# Interface_USB3.net
KiCad netlist of a schematic drawn in EAGLE
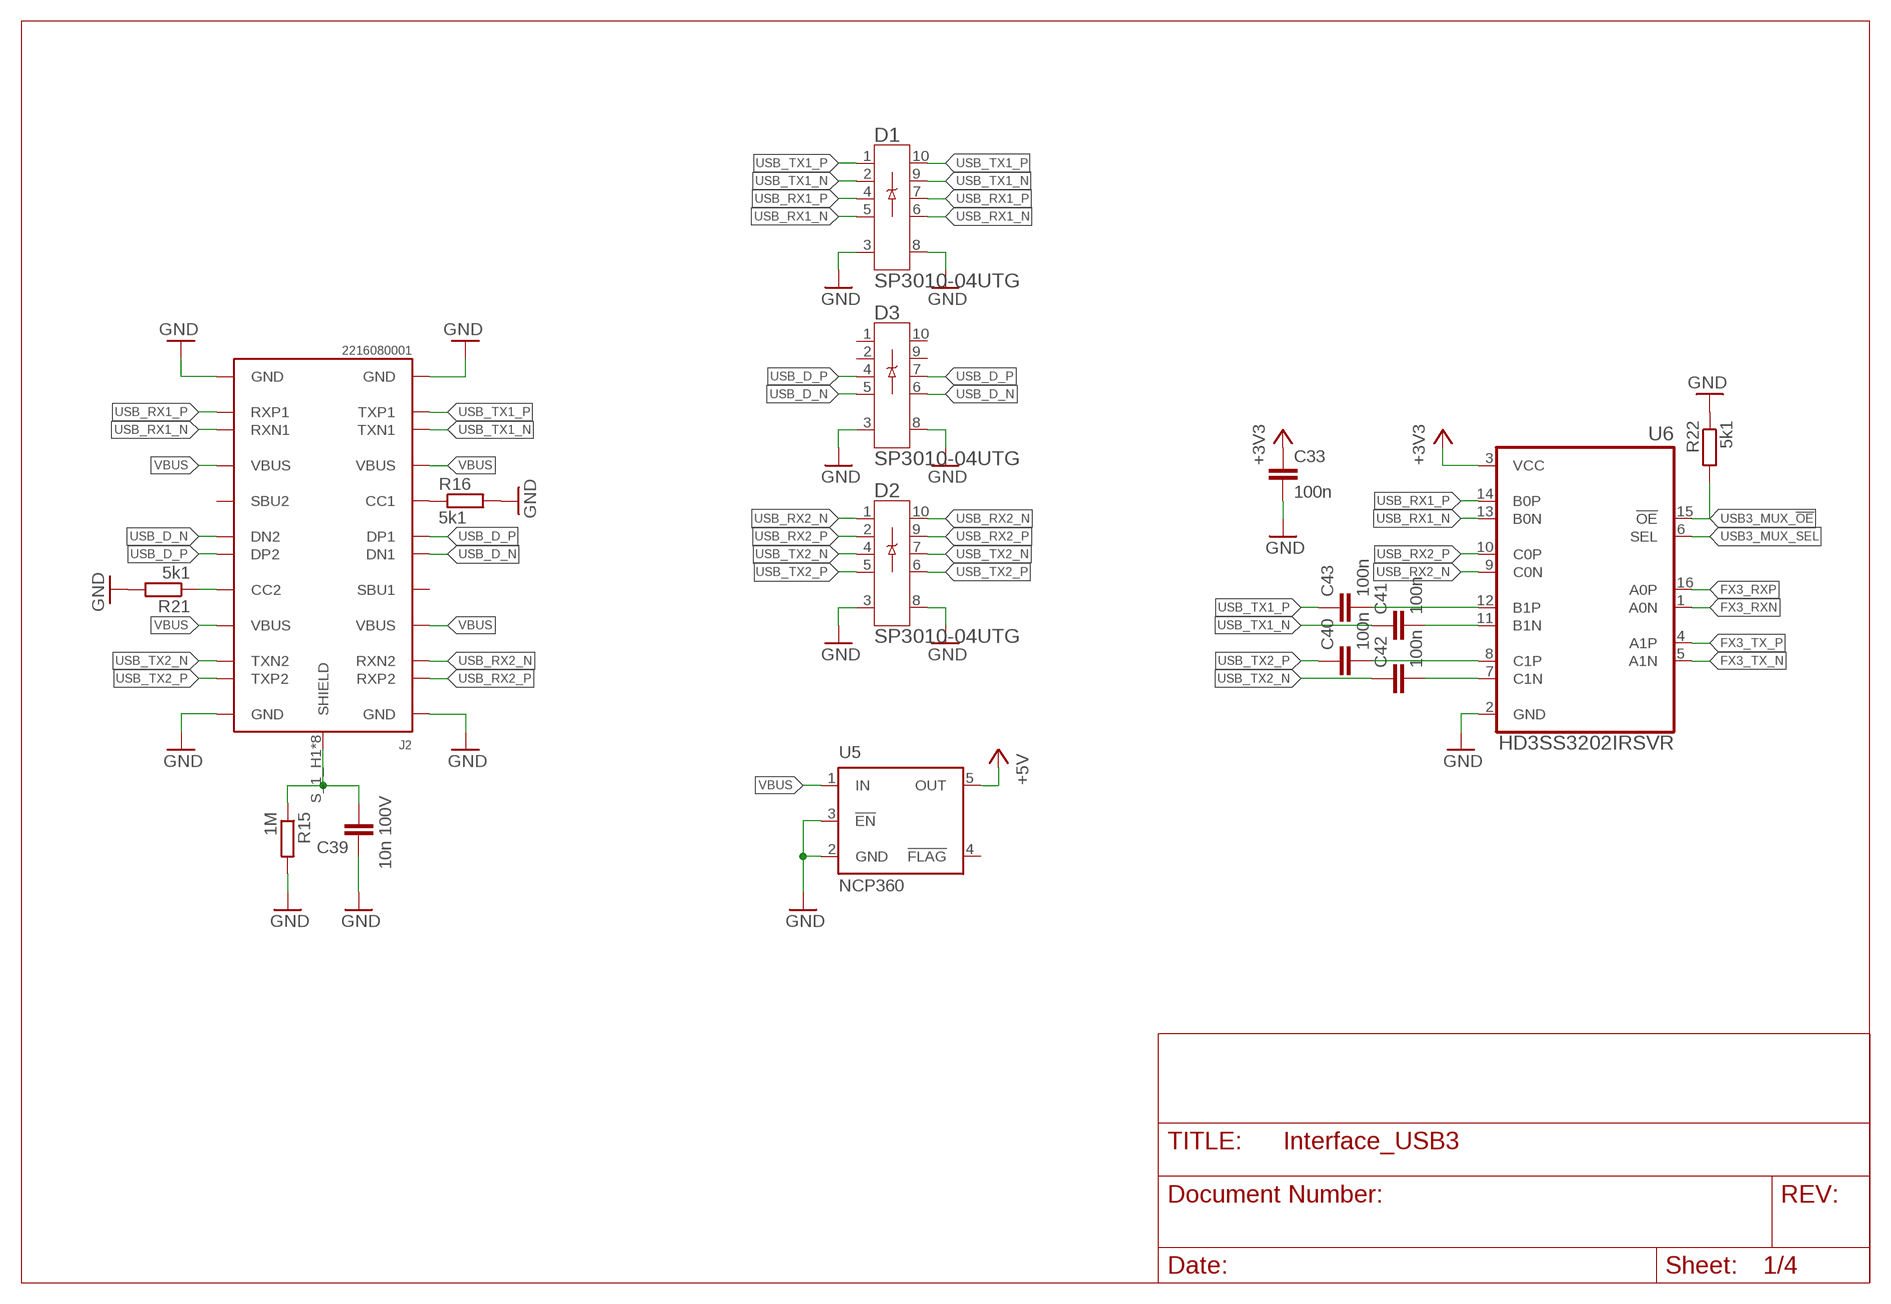
[diagram p0: schematic, sheet 1]
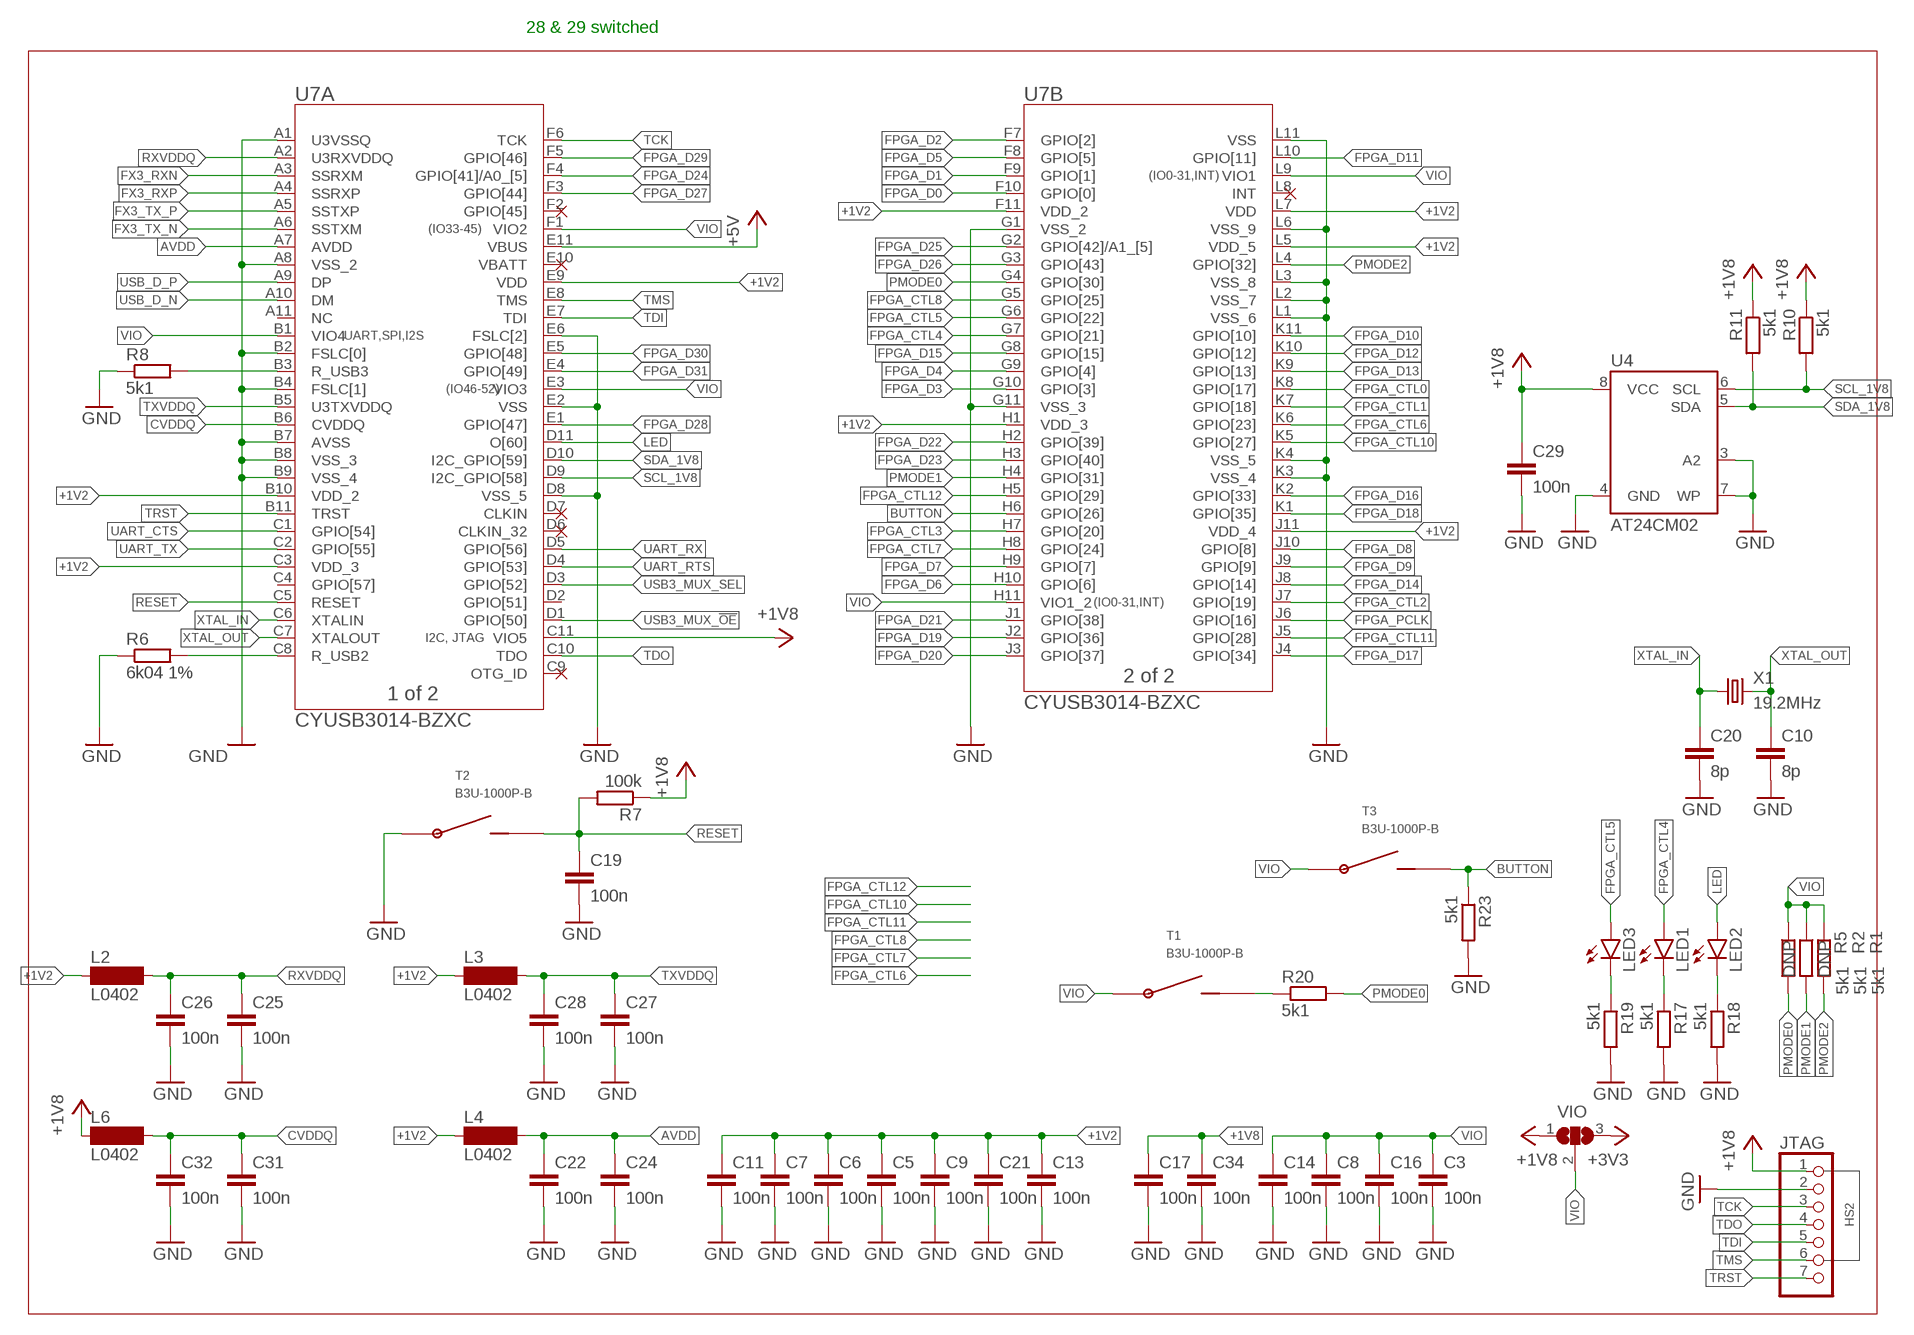
[diagram p1: schematic, sheet 2]
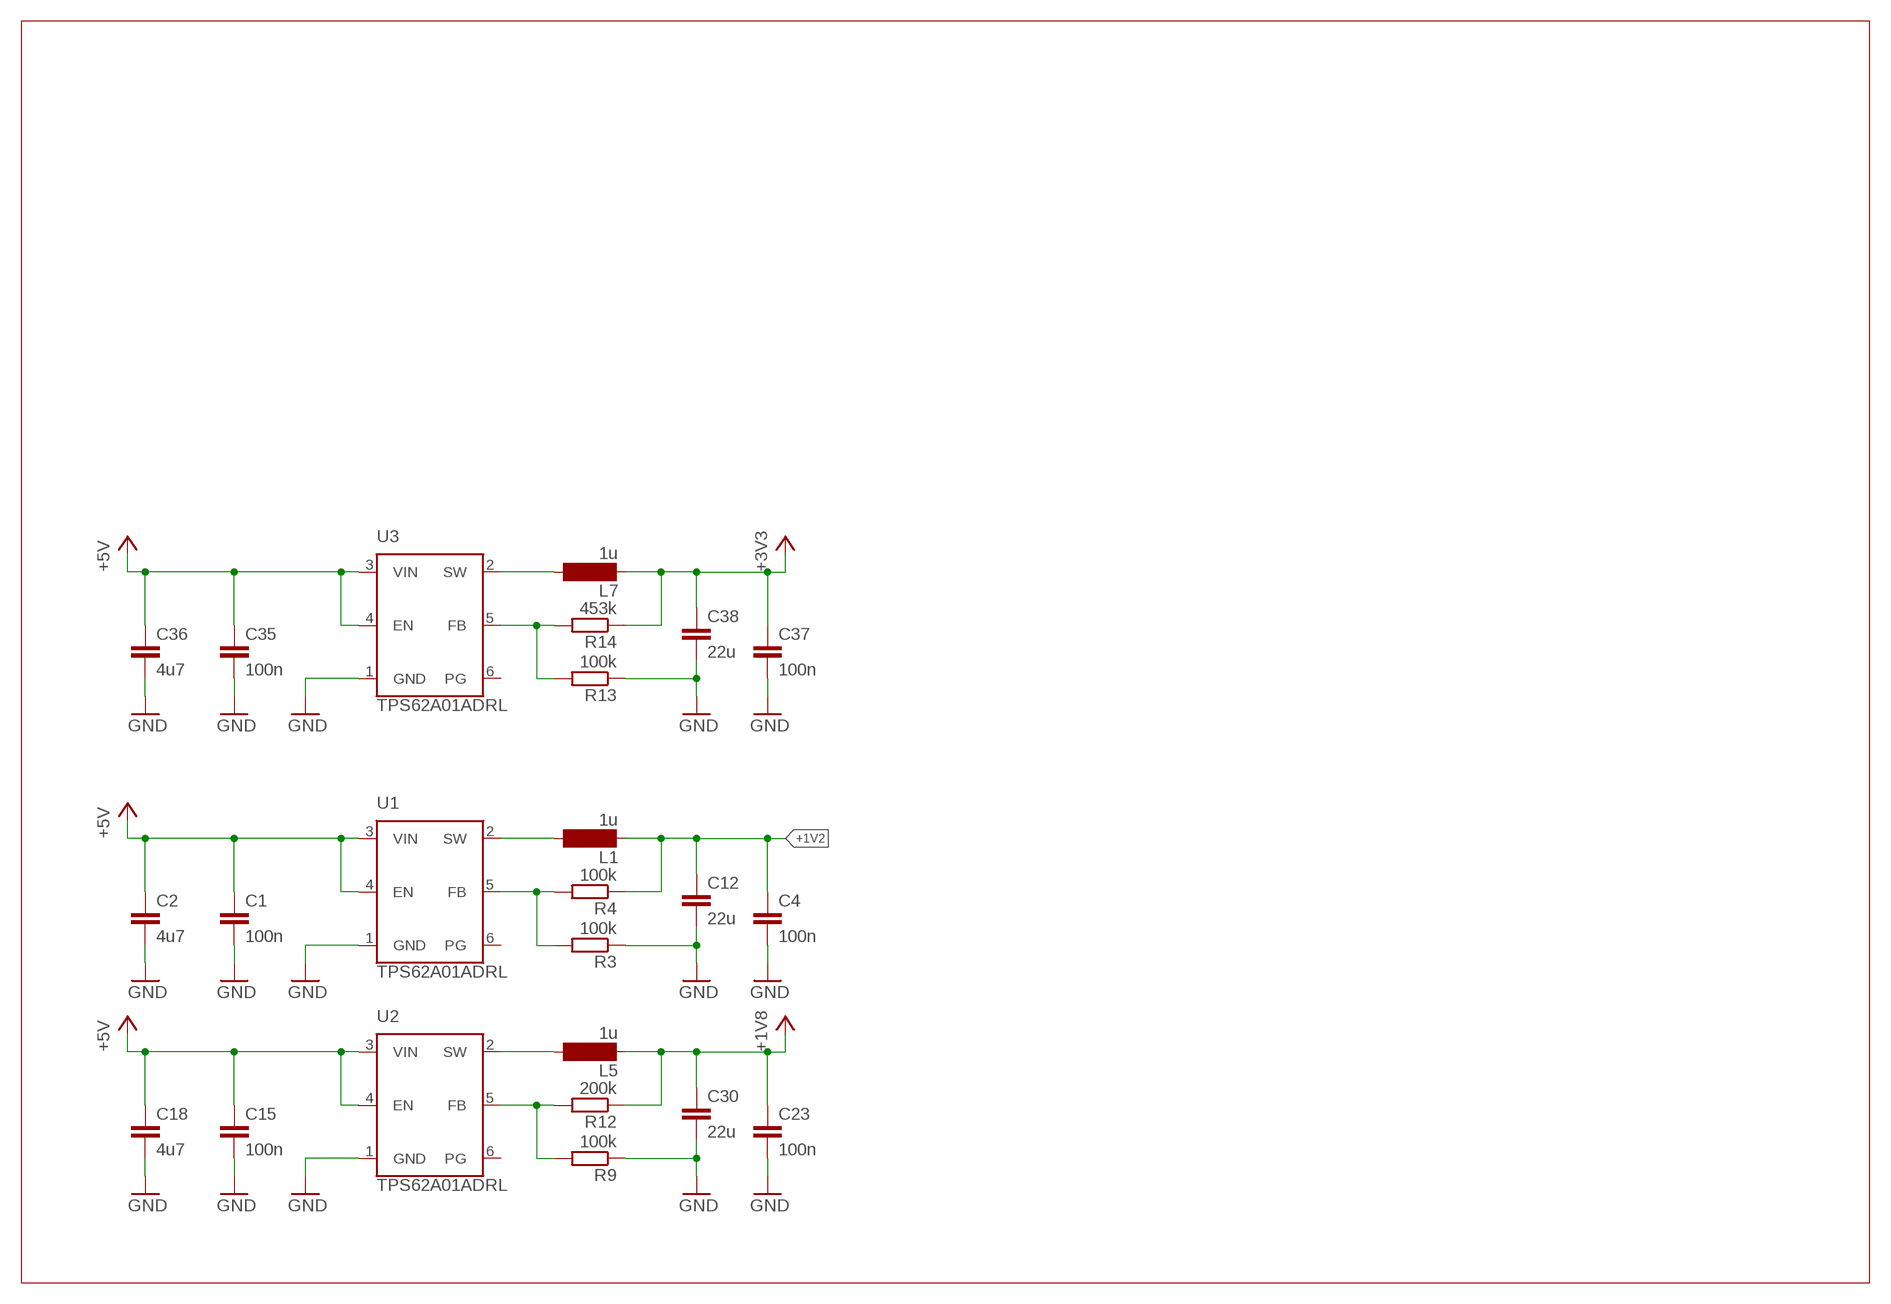
[diagram p2: schematic, sheet 3]
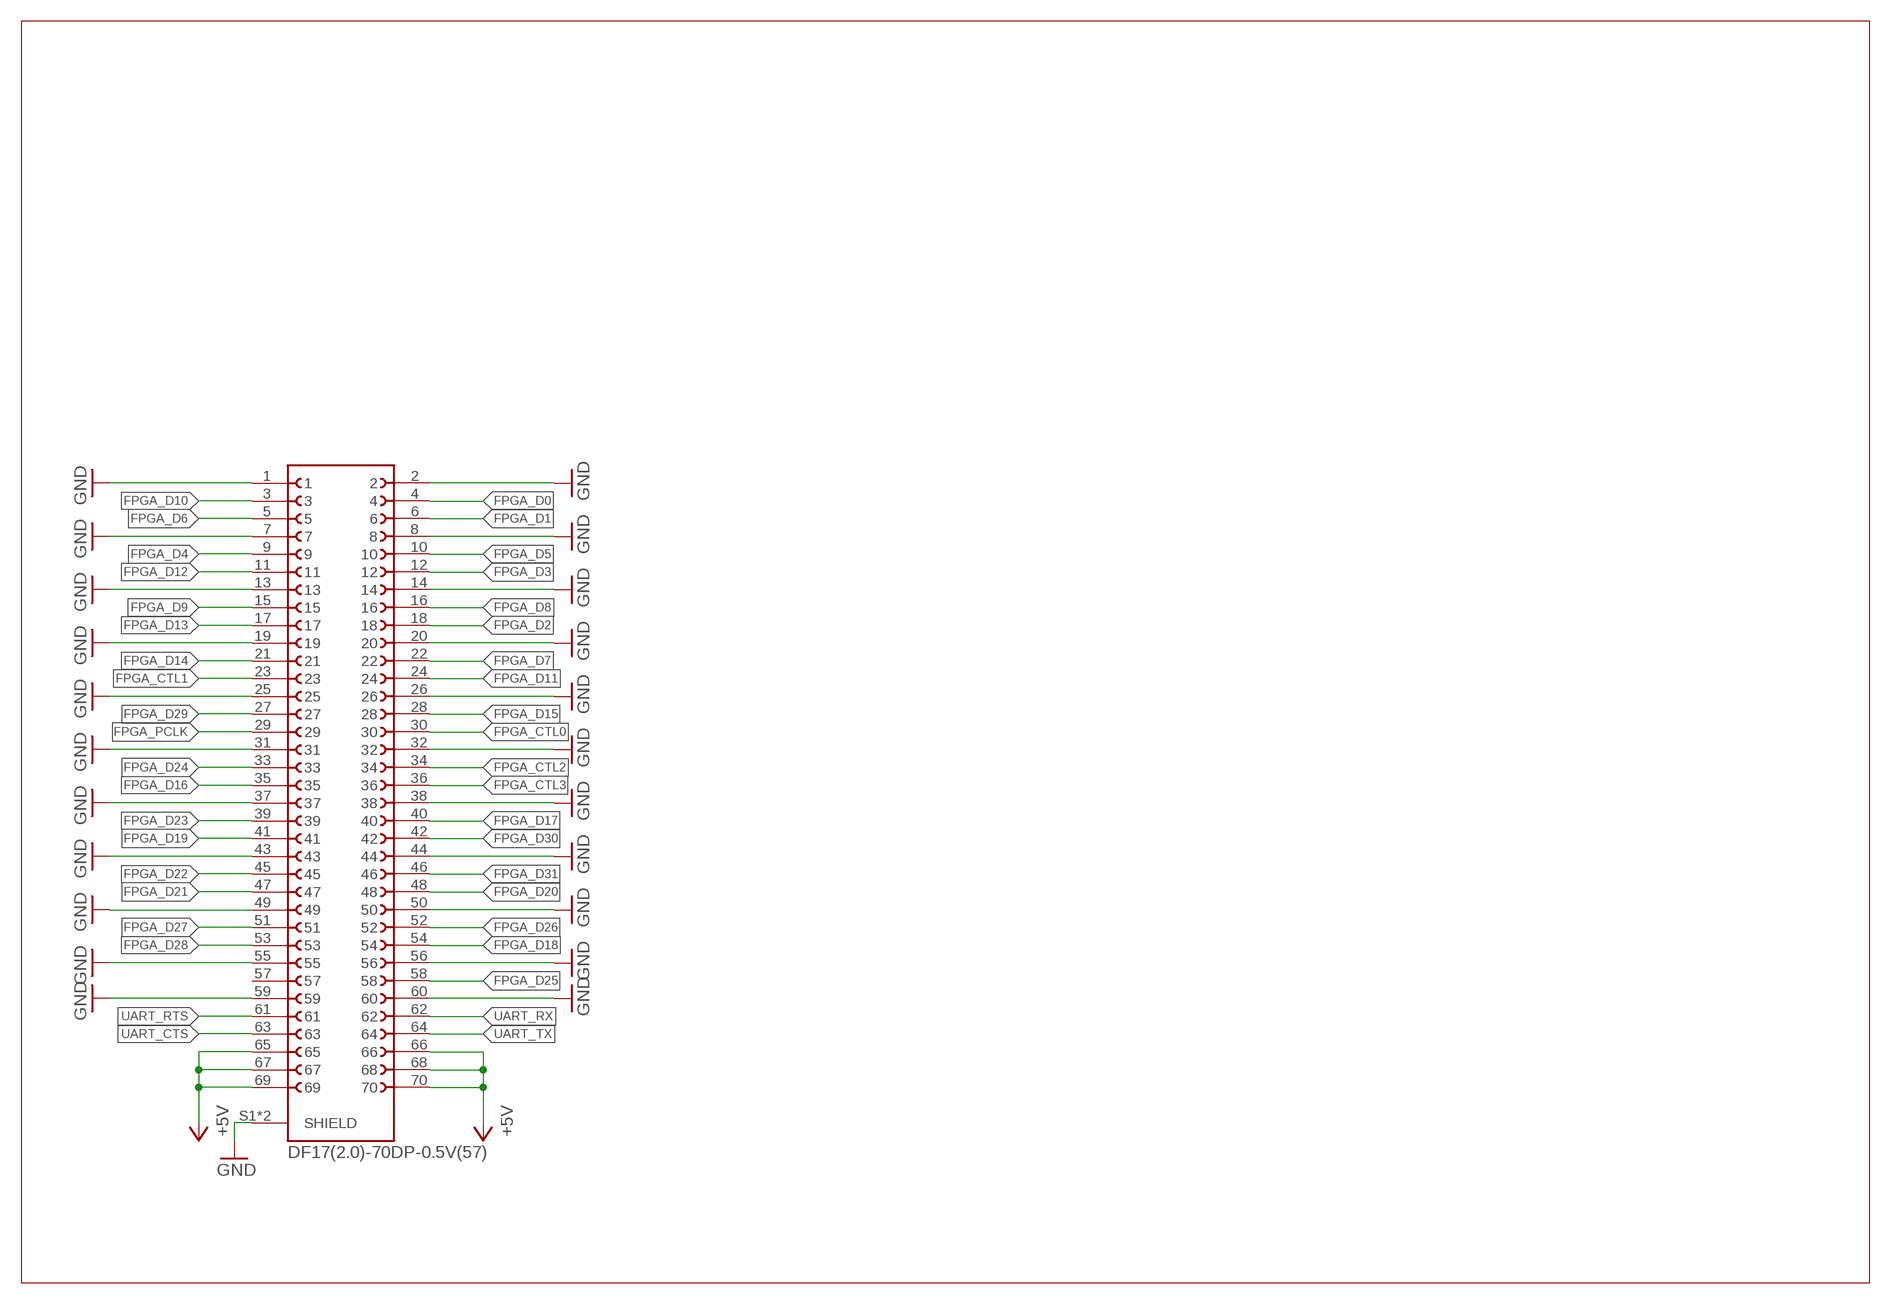
[diagram p3: schematic, sheet 4]

(export (version "E")
  (design (tool "Eeschema 10.0.6"))
  (components
    (comp (ref "C33")
      (value "100n")
      (footprint "eagle-import:C0402")
      (libsource (lib "eagle-import") (part "C0402"))
    )
    (comp (ref "C39")
      (value "10n 100V")
      (footprint "eagle-import:C0603")
      (libsource (lib "eagle-import") (part "rcl_334_C-EUC0603"))
    )
    (comp (ref "C40")
      (value "100n")
      (footprint "eagle-import:C0402")
      (libsource (lib "eagle-import") (part "C0402"))
    )
    (comp (ref "C41")
      (value "100n")
      (footprint "eagle-import:C0402")
      (libsource (lib "eagle-import") (part "C0402"))
    )
    (comp (ref "C42")
      (value "100n")
      (footprint "eagle-import:C0402")
      (libsource (lib "eagle-import") (part "C0402"))
    )
    (comp (ref "C43")
      (value "100n")
      (footprint "eagle-import:C0402")
      (libsource (lib "eagle-import") (part "C0402"))
    )
    (comp (ref "D1")
      (value "SP3010-04UTG")
      (footprint "eagle-import:UDFEN-10_MO229_LTF")
      (libsource (lib "eagle-import") (part "SP3010-04UTG"))
    )
    (comp (ref "D2")
      (value "SP3010-04UTG")
      (footprint "eagle-import:UDFEN-10_MO229_LTF")
      (libsource (lib "eagle-import") (part "SP3010-04UTG"))
    )
    (comp (ref "D3")
      (value "SP3010-04UTG")
      (footprint "eagle-import:UDFEN-10_MO229_LTF")
      (libsource (lib "eagle-import") (part "SP3010-04UTG"))
    )
    (comp (ref "J2")
      (value "2216080001")
      (footprint "eagle-import:CONN_221608-0001_MOL")
      (libsource (lib "eagle-import") (part "2216080001"))
    )
    (comp (ref "R15")
      (value "1M")
      (footprint "eagle-import:R0603")
      (libsource (lib "eagle-import") (part "R-EU_R0603"))
    )
    (comp (ref "R16")
      (value "5k1")
      (footprint "eagle-import:R0402")
      (libsource (lib "eagle-import") (part "R-EU_R0402"))
    )
    (comp (ref "R21")
      (value "5k1")
      (footprint "eagle-import:R0402")
      (libsource (lib "eagle-import") (part "R-EU_R0402"))
    )
    (comp (ref "R22")
      (value "5k1")
      (footprint "eagle-import:R0402")
      (libsource (lib "eagle-import") (part "R-EU_R0402"))
    )
    (comp (ref "U5")
      (value "NCP360")
      (footprint "eagle-import:TSOP-5")
      (libsource (lib "eagle-import") (part "NCP360"))
    )
    (comp (ref "U6")
      (value "HD3SS3202IRSVR")
      (footprint "eagle-import:QFN40P180X260X55-16N_HD3SS3202IRSVR")
      (fields (field (name "MANUFACTURER") "Texas Instruments"))
      (libsource (lib "eagle-import") (part "HD3SS3202IRSVR"))
    )
    (comp (ref "C3")
      (value "100n")
      (footprint "eagle-import:C0402")
      (libsource (lib "eagle-import") (part "C0402"))
    )
    (comp (ref "C5")
      (value "100n")
      (footprint "eagle-import:C0402")
      (libsource (lib "eagle-import") (part "C0402"))
    )
    (comp (ref "C6")
      (value "100n")
      (footprint "eagle-import:C0402")
      (libsource (lib "eagle-import") (part "C0402"))
    )
    (comp (ref "C7")
      (value "100n")
      (footprint "eagle-import:C0402")
      (libsource (lib "eagle-import") (part "C0402"))
    )
    (comp (ref "C8")
      (value "100n")
      (footprint "eagle-import:C0402")
      (libsource (lib "eagle-import") (part "C0402"))
    )
    (comp (ref "C9")
      (value "100n")
      (footprint "eagle-import:C0402")
      (libsource (lib "eagle-import") (part "C0402"))
    )
    (comp (ref "C10")
      (value "8p")
      (footprint "eagle-import:C0402")
      (libsource (lib "eagle-import") (part "C0402"))
    )
    (comp (ref "C11")
      (value "100n")
      (footprint "eagle-import:C0402")
      (libsource (lib "eagle-import") (part "C0402"))
    )
    (comp (ref "C13")
      (value "100n")
      (footprint "eagle-import:C0402")
      (libsource (lib "eagle-import") (part "C0402"))
    )
    (comp (ref "C14")
      (value "100n")
      (footprint "eagle-import:C0402")
      (libsource (lib "eagle-import") (part "C0402"))
    )
    (comp (ref "C16")
      (value "100n")
      (footprint "eagle-import:C0402")
      (libsource (lib "eagle-import") (part "C0402"))
    )
    (comp (ref "C17")
      (value "100n")
      (footprint "eagle-import:C0402")
      (libsource (lib "eagle-import") (part "C0402"))
    )
    (comp (ref "C19")
      (value "100n")
      (footprint "eagle-import:C0402")
      (libsource (lib "eagle-import") (part "C0402"))
    )
    (comp (ref "C20")
      (value "8p")
      (footprint "eagle-import:C0402")
      (libsource (lib "eagle-import") (part "C0402"))
    )
    (comp (ref "C21")
      (value "100n")
      (footprint "eagle-import:C0402")
      (libsource (lib "eagle-import") (part "C0402"))
    )
    (comp (ref "C22")
      (value "100n")
      (footprint "eagle-import:C0402")
      (libsource (lib "eagle-import") (part "C0402"))
    )
    (comp (ref "C24")
      (value "100n")
      (footprint "eagle-import:C0402")
      (libsource (lib "eagle-import") (part "C0402"))
    )
    (comp (ref "C25")
      (value "100n")
      (footprint "eagle-import:C0402")
      (libsource (lib "eagle-import") (part "C0402"))
    )
    (comp (ref "C26")
      (value "100n")
      (footprint "eagle-import:C0402")
      (libsource (lib "eagle-import") (part "C0402"))
    )
    (comp (ref "C27")
      (value "100n")
      (footprint "eagle-import:C0402")
      (libsource (lib "eagle-import") (part "C0402"))
    )
    (comp (ref "C28")
      (value "100n")
      (footprint "eagle-import:C0402")
      (libsource (lib "eagle-import") (part "C0402"))
    )
    (comp (ref "C29")
      (value "100n")
      (footprint "eagle-import:C0402")
      (libsource (lib "eagle-import") (part "C0402"))
    )
    (comp (ref "C31")
      (value "100n")
      (footprint "eagle-import:C0402")
      (libsource (lib "eagle-import") (part "C0402"))
    )
    (comp (ref "C32")
      (value "100n")
      (footprint "eagle-import:C0402")
      (libsource (lib "eagle-import") (part "C0402"))
    )
    (comp (ref "C34")
      (value "100n")
      (footprint "eagle-import:C0402")
      (libsource (lib "eagle-import") (part "C0402"))
    )
    (comp (ref "JTAG")
      (value "PINHD-1X7_2.00")
      (footprint "eagle-import:1X07M")
      (libsource (lib "eagle-import") (part "PINHD-1X7_2.00"))
    )
    (comp (ref "L2")
      (value "L0402")
      (footprint "eagle-import:C0402")
      (libsource (lib "eagle-import") (part "L0402"))
    )
    (comp (ref "L3")
      (value "L0402")
      (footprint "eagle-import:C0402")
      (libsource (lib "eagle-import") (part "L0402"))
    )
    (comp (ref "L4")
      (value "L0402")
      (footprint "eagle-import:C0402")
      (libsource (lib "eagle-import") (part "L0402"))
    )
    (comp (ref "L6")
      (value "L0402")
      (footprint "eagle-import:C0402")
      (libsource (lib "eagle-import") (part "L0402"))
    )
    (comp (ref "LED1")
      (value "LEDCHIPLED_0603")
      (footprint "eagle-import:CHIPLED_0603")
      (libsource (lib "eagle-import") (part "LEDCHIPLED_0603"))
    )
    (comp (ref "LED2")
      (value "LEDCHIPLED_0603")
      (footprint "eagle-import:CHIPLED_0603")
      (libsource (lib "eagle-import") (part "LEDCHIPLED_0603"))
    )
    (comp (ref "LED3")
      (value "LEDCHIPLED_0603")
      (footprint "eagle-import:CHIPLED_0603")
      (libsource (lib "eagle-import") (part "LEDCHIPLED_0603"))
    )
    (comp (ref "R1")
      (value "5k1")
      (footprint "eagle-import:R0402")
      (fields (field (name "DNP") "DNP"))
      (libsource (lib "eagle-import") (part "R-EU_R0402"))
    )
    (comp (ref "R2")
      (value "5k1")
      (footprint "eagle-import:R0402")
      (libsource (lib "eagle-import") (part "R-EU_R0402"))
    )
    (comp (ref "R5")
      (value "5k1")
      (footprint "eagle-import:R0402")
      (fields (field (name "DNP") "DNP"))
      (libsource (lib "eagle-import") (part "R-EU_R0402"))
    )
    (comp (ref "R6")
      (value "6k04 1%")
      (footprint "eagle-import:R0402")
      (libsource (lib "eagle-import") (part "R-EU_R0402"))
    )
    (comp (ref "R7")
      (value "100k")
      (footprint "eagle-import:R0402")
      (libsource (lib "eagle-import") (part "R-EU_R0402"))
    )
    (comp (ref "R8")
      (value "5k1")
      (footprint "eagle-import:R0402")
      (libsource (lib "eagle-import") (part "R-EU_R0402"))
    )
    (comp (ref "R10")
      (value "5k1")
      (footprint "eagle-import:R0402")
      (libsource (lib "eagle-import") (part "R-EU_R0402"))
    )
    (comp (ref "R11")
      (value "5k1")
      (footprint "eagle-import:R0402")
      (libsource (lib "eagle-import") (part "R-EU_R0402"))
    )
    (comp (ref "R17")
      (value "5k1")
      (footprint "eagle-import:R0402")
      (libsource (lib "eagle-import") (part "R-EU_R0402"))
    )
    (comp (ref "R18")
      (value "5k1")
      (footprint "eagle-import:R0402")
      (libsource (lib "eagle-import") (part "R-EU_R0402"))
    )
    (comp (ref "R19")
      (value "5k1")
      (footprint "eagle-import:R0402")
      (libsource (lib "eagle-import") (part "R-EU_R0402"))
    )
    (comp (ref "R20")
      (value "5k1")
      (footprint "eagle-import:R0402")
      (libsource (lib "eagle-import") (part "R-EU_R0402"))
    )
    (comp (ref "R23")
      (value "5k1")
      (footprint "eagle-import:R0402")
      (libsource (lib "eagle-import") (part "R-EU_R0402"))
    )
    (comp (ref "T1")
      (value "B3U-1000P-B")
      (footprint "eagle-import:B3U-1000P-B")
      (libsource (lib "eagle-import") (part "B3U-1000P-B"))
    )
    (comp (ref "T2")
      (value "B3U-1000P-B")
      (footprint "eagle-import:B3U-1000P-B")
      (libsource (lib "eagle-import") (part "B3U-1000P-B"))
    )
    (comp (ref "T3")
      (value "B3U-1000P-B")
      (footprint "eagle-import:B3U-1000P-B")
      (libsource (lib "eagle-import") (part "B3U-1000P-B"))
    )
    (comp (ref "U4")
      (value "AT24CM02")
      (footprint "eagle-import:SOIC8")
      (libsource (lib "eagle-import") (part "AT24CM02"))
    )
    (comp (ref "U7")
      (value "CYUSB3014-BZXC")
      (footprint "eagle-import:PG-TFBGA-121-800_INF")
      (fields (field (name "LCSC") "C462526"))
      (libsource (lib "eagle-import") (part "CYUSB3014-BZXC"))
    )
    (comp (ref "VIO")
      (value "SJ2W")
      (footprint "eagle-import:SJ_2")
      (libsource (lib "eagle-import") (part "SJ2W"))
    )
    (comp (ref "X1")
      (value "19.2MHz")
      (footprint "eagle-import:2520")
      (libsource (lib "eagle-import") (part "CRYSTAL-2520"))
    )
    (comp (ref "C1")
      (value "100n")
      (footprint "eagle-import:C0402")
      (libsource (lib "eagle-import") (part "C0402"))
    )
    (comp (ref "C2")
      (value "4u7")
      (footprint "eagle-import:C0603")
      (libsource (lib "eagle-import") (part "C-EUC0603"))
    )
    (comp (ref "C4")
      (value "100n")
      (footprint "eagle-import:C0402")
      (libsource (lib "eagle-import") (part "C0402"))
    )
    (comp (ref "C12")
      (value "22u")
      (footprint "eagle-import:C0603")
      (libsource (lib "eagle-import") (part "C-EUC0603"))
    )
    (comp (ref "C15")
      (value "100n")
      (footprint "eagle-import:C0402")
      (libsource (lib "eagle-import") (part "C0402"))
    )
    (comp (ref "C18")
      (value "4u7")
      (footprint "eagle-import:C0603")
      (libsource (lib "eagle-import") (part "C-EUC0603"))
    )
    (comp (ref "C23")
      (value "100n")
      (footprint "eagle-import:C0402")
      (libsource (lib "eagle-import") (part "C0402"))
    )
    (comp (ref "C30")
      (value "22u")
      (footprint "eagle-import:C0603")
      (libsource (lib "eagle-import") (part "C-EUC0603"))
    )
    (comp (ref "C35")
      (value "100n")
      (footprint "eagle-import:C0402")
      (libsource (lib "eagle-import") (part "C0402"))
    )
    (comp (ref "C36")
      (value "4u7")
      (footprint "eagle-import:C0603")
      (libsource (lib "eagle-import") (part "C-EUC0603"))
    )
    (comp (ref "C37")
      (value "100n")
      (footprint "eagle-import:C0402")
      (libsource (lib "eagle-import") (part "C0402"))
    )
    (comp (ref "C38")
      (value "22u")
      (footprint "eagle-import:C0603")
      (libsource (lib "eagle-import") (part "C-EUC0603"))
    )
    (comp (ref "L1")
      (value "1u")
      (footprint "eagle-import:L1008")
      (fields (field (name "MPN") "LQM2HPN1R0MG0L"))
      (libsource (lib "eagle-import") (part "L1008"))
    )
    (comp (ref "L5")
      (value "1u")
      (footprint "eagle-import:L1008")
      (fields (field (name "MPN") "LQM2HPN1R0MG0L"))
      (libsource (lib "eagle-import") (part "L1008"))
    )
    (comp (ref "L7")
      (value "1u")
      (footprint "eagle-import:L1008")
      (fields (field (name "MPN") "LQM2HPN1R0MG0L"))
      (libsource (lib "eagle-import") (part "L1008"))
    )
    (comp (ref "R3")
      (value "100k")
      (footprint "eagle-import:R0402")
      (libsource (lib "eagle-import") (part "R-EU_R0402"))
    )
    (comp (ref "R4")
      (value "100k")
      (footprint "eagle-import:R0402")
      (libsource (lib "eagle-import") (part "R-EU_R0402"))
    )
    (comp (ref "R9")
      (value "100k")
      (footprint "eagle-import:R0402")
      (libsource (lib "eagle-import") (part "R-EU_R0402"))
    )
    (comp (ref "R12")
      (value "200k")
      (footprint "eagle-import:R0402")
      (libsource (lib "eagle-import") (part "R-EU_R0402"))
    )
    (comp (ref "R13")
      (value "100k")
      (footprint "eagle-import:R0402")
      (libsource (lib "eagle-import") (part "R-EU_R0402"))
    )
    (comp (ref "R14")
      (value "453k")
      (footprint "eagle-import:R0402")
      (libsource (lib "eagle-import") (part "R-EU_R0402"))
    )
    (comp (ref "U1")
      (value "TPS62A01ADRL")
      (footprint "eagle-import:SOTFL50P160X60-6N")
      (fields (field (name "MANUFACTURER_PART_NUMBER") "TPS62A01ADRLR"))
      (libsource (lib "eagle-import") (part "TPS62A01ADRL"))
    )
    (comp (ref "U2")
      (value "TPS62A01ADRL")
      (footprint "eagle-import:SOTFL50P160X60-6N")
      (fields (field (name "MANUFACTURER_PART_NUMBER") "TPS62A01ADRLR"))
      (libsource (lib "eagle-import") (part "TPS62A01ADRL"))
    )
    (comp (ref "U3")
      (value "TPS62A01ADRL")
      (footprint "eagle-import:SOTFL50P160X60-6N")
      (fields (field (name "MANUFACTURER_PART_NUMBER") "TPS62A01ADRLR"))
      (libsource (lib "eagle-import") (part "TPS62A01ADRL"))
    )
    (comp (ref "J1")
      (value "DF17(2.0)-70DP-0.5V(57)")
      (footprint "eagle-import:DF17(2.0)-70DP-0.5V(57)")
      (libsource (lib "eagle-import") (part "DF17(2.0)-70DP-0.5V(57)"))
    )
  )
  (nets
    (net (code "1") (name "+1V2") (class "Default")
      (node (ref "C11") (pin "1") (pinfunction "1_1") (pintype "passive"))
      (node (ref "C12") (pin "1") (pinfunction "1_1") (pintype "passive"))
      (node (ref "C13") (pin "1") (pinfunction "1_1") (pintype "passive"))
      (node (ref "C21") (pin "1") (pinfunction "1_1") (pintype "passive"))
      (node (ref "C4") (pin "1") (pinfunction "1_1") (pintype "passive"))
      (node (ref "C5") (pin "1") (pinfunction "1_1") (pintype "passive"))
      (node (ref "C6") (pin "1") (pinfunction "1_1") (pintype "passive"))
      (node (ref "C7") (pin "1") (pinfunction "1_1") (pintype "passive"))
      (node (ref "C9") (pin "1") (pinfunction "1_1") (pintype "passive"))
      (node (ref "L1") (pin "1") (pinfunction "1_1") (pintype "passive"))
      (node (ref "L2") (pin "1") (pinfunction "1_1") (pintype "passive"))
      (node (ref "L3") (pin "1") (pinfunction "1_1") (pintype "passive"))
      (node (ref "L4") (pin "1") (pinfunction "1_1") (pintype "passive"))
      (node (ref "R4") (pin "1") (pinfunction "1_1") (pintype "passive"))
      (node (ref "U7") (pin "B10") (pinfunction "VDD_2_B10") (pintype "power_in"))
      (node (ref "U7") (pin "C3") (pinfunction "VDD_3_C3") (pintype "power_in"))
      (node (ref "U7") (pin "E9") (pinfunction "VDD_E9") (pintype "power_in"))
      (node (ref "U7") (pin "F11") (pinfunction "VDD_2_F11") (pintype "power_in"))
      (node (ref "U7") (pin "H1") (pinfunction "VDD_3_H1") (pintype "power_in"))
      (node (ref "U7") (pin "J11") (pinfunction "VDD_4_J11") (pintype "power_in"))
      (node (ref "U7") (pin "L5") (pinfunction "VDD_5_L5") (pintype "power_in"))
      (node (ref "U7") (pin "L7") (pinfunction "VDD_L7") (pintype "power_in"))
    )
    (net (code "2") (name "+1V8") (class "Default")
      (node (ref "C17") (pin "1") (pinfunction "1_1") (pintype "passive"))
      (node (ref "C23") (pin "1") (pinfunction "1_1") (pintype "passive"))
      (node (ref "C29") (pin "1") (pinfunction "1_1") (pintype "passive"))
      (node (ref "C30") (pin "1") (pinfunction "1_1") (pintype "passive"))
      (node (ref "C34") (pin "1") (pinfunction "1_1") (pintype "passive"))
      (node (ref "JTAG") (pin "1") (pinfunction "1_1") (pintype "passive"))
      (node (ref "L5") (pin "1") (pinfunction "1_1") (pintype "passive"))
      (node (ref "L6") (pin "1") (pinfunction "1_1") (pintype "passive"))
      (node (ref "R10") (pin "1") (pinfunction "1_1") (pintype "passive"))
      (node (ref "R11") (pin "1") (pinfunction "1_1") (pintype "passive"))
      (node (ref "R12") (pin "1") (pinfunction "1_1") (pintype "passive"))
      (node (ref "R7") (pin "1") (pinfunction "1_1") (pintype "passive"))
      (node (ref "U4") (pin "8") (pinfunction "VCC_8") (pintype "power_in"))
      (node (ref "U7") (pin "C11") (pinfunction "VIO5_C11") (pintype "bidirectional"))
      (node (ref "VIO") (pin "1") (pinfunction "1_1") (pintype "passive"))
    )
    (net (code "3") (name "+3V3") (class "Default")
      (node (ref "C33") (pin "1") (pinfunction "1_1") (pintype "passive"))
      (node (ref "C37") (pin "1") (pinfunction "1_1") (pintype "passive"))
      (node (ref "C38") (pin "1") (pinfunction "1_1") (pintype "passive"))
      (node (ref "L7") (pin "1") (pinfunction "1_1") (pintype "passive"))
      (node (ref "R14") (pin "1") (pinfunction "1_1") (pintype "passive"))
      (node (ref "U6") (pin "3") (pinfunction "VCC_3") (pintype "power_in"))
      (node (ref "VIO") (pin "3") (pinfunction "3_3") (pintype "passive"))
    )
    (net (code "4") (name "+5V") (class "Default")
      (node (ref "C1") (pin "1") (pinfunction "1_1") (pintype "passive"))
      (node (ref "C15") (pin "1") (pinfunction "1_1") (pintype "passive"))
      (node (ref "C18") (pin "1") (pinfunction "1_1") (pintype "passive"))
      (node (ref "C2") (pin "1") (pinfunction "1_1") (pintype "passive"))
      (node (ref "C35") (pin "1") (pinfunction "1_1") (pintype "passive"))
      (node (ref "C36") (pin "1") (pinfunction "1_1") (pintype "passive"))
      (node (ref "J1") (pin "65") (pinfunction "65_65") (pintype "passive"))
      (node (ref "J1") (pin "66") (pinfunction "66_66") (pintype "passive"))
      (node (ref "J1") (pin "67") (pinfunction "67_67") (pintype "passive"))
      (node (ref "J1") (pin "68") (pinfunction "68_68") (pintype "passive"))
      (node (ref "J1") (pin "69") (pinfunction "69_69") (pintype "passive"))
      (node (ref "J1") (pin "70") (pinfunction "70_70") (pintype "passive"))
      (node (ref "U1") (pin "3") (pinfunction "VIN_3") (pintype "bidirectional"))
      (node (ref "U1") (pin "4") (pinfunction "EN_4") (pintype "bidirectional"))
      (node (ref "U2") (pin "3") (pinfunction "VIN_3") (pintype "bidirectional"))
      (node (ref "U2") (pin "4") (pinfunction "EN_4") (pintype "bidirectional"))
      (node (ref "U3") (pin "3") (pinfunction "VIN_3") (pintype "bidirectional"))
      (node (ref "U3") (pin "4") (pinfunction "EN_4") (pintype "bidirectional"))
      (node (ref "U5") (pin "5") (pinfunction "OUT_5") (pintype "passive"))
      (node (ref "U7") (pin "E11") (pinfunction "VBUS_E11") (pintype "power_in"))
    )
    (net (code "5") (name "AVDD") (class "Default")
      (node (ref "C22") (pin "1") (pinfunction "1_1") (pintype "passive"))
      (node (ref "C24") (pin "1") (pinfunction "1_1") (pintype "passive"))
      (node (ref "L4") (pin "2") (pinfunction "2_2") (pintype "passive"))
      (node (ref "U7") (pin "A7") (pinfunction "AVDD_A7") (pintype "power_in"))
    )
    (net (code "6") (name "BUTTON") (class "Default")
      (node (ref "R23") (pin "1") (pinfunction "1_1") (pintype "passive"))
      (node (ref "T3") (pin "P$2") (pinfunction "P$2_P$2") (pintype "bidirectional"))
      (node (ref "U7") (pin "H6") (pinfunction "GPIO[26]_H6") (pintype "bidirectional"))
    )
    (net (code "7") (name "CVDDQ") (class "Default")
      (node (ref "C31") (pin "1") (pinfunction "1_1") (pintype "passive"))
      (node (ref "C32") (pin "1") (pinfunction "1_1") (pintype "passive"))
      (node (ref "L6") (pin "2") (pinfunction "2_2") (pintype "passive"))
      (node (ref "U7") (pin "B6") (pinfunction "CVDDQ_B6") (pintype "power_in"))
    )
    (net (code "8") (name "FPGA_CTL0") (class "Default")
      (node (ref "J1") (pin "30") (pinfunction "30_30") (pintype "passive"))
      (node (ref "U7") (pin "K8") (pinfunction "GPIO[17]_K8") (pintype "bidirectional"))
    )
    (net (code "9") (name "FPGA_CTL1") (class "Default")
      (node (ref "J1") (pin "23") (pinfunction "23_23") (pintype "passive"))
      (node (ref "U7") (pin "K7") (pinfunction "GPIO[18]_K7") (pintype "bidirectional"))
    )
    (net (code "10") (name "FPGA_CTL2") (class "Default")
      (node (ref "J1") (pin "34") (pinfunction "34_34") (pintype "passive"))
      (node (ref "U7") (pin "J7") (pinfunction "GPIO[19]_J7") (pintype "bidirectional"))
    )
    (net (code "11") (name "FPGA_CTL3") (class "Default")
      (node (ref "J1") (pin "36") (pinfunction "36_36") (pintype "passive"))
      (node (ref "U7") (pin "H7") (pinfunction "GPIO[20]_H7") (pintype "bidirectional"))
    )
    (net (code "12") (name "FPGA_CTL4") (class "Default")
      (node (ref "LED1") (pin "A") (pinfunction "A_A") (pintype "passive"))
      (node (ref "U7") (pin "G7") (pinfunction "GPIO[21]_G7") (pintype "bidirectional"))
    )
    (net (code "13") (name "FPGA_CTL5") (class "Default")
      (node (ref "LED3") (pin "A") (pinfunction "A_A") (pintype "passive"))
      (node (ref "U7") (pin "G6") (pinfunction "GPIO[22]_G6") (pintype "bidirectional"))
    )
    (net (code "14") (name "FPGA_CTL6") (class "Default")
      (node (ref "U7") (pin "K6") (pinfunction "GPIO[23]_K6") (pintype "bidirectional"))
    )
    (net (code "15") (name "FPGA_CTL7") (class "Default")
      (node (ref "U7") (pin "H8") (pinfunction "GPIO[24]_H8") (pintype "bidirectional"))
    )
    (net (code "16") (name "FPGA_CTL8") (class "Default")
      (node (ref "U7") (pin "G5") (pinfunction "GPIO[25]_G5") (pintype "bidirectional"))
    )
    (net (code "17") (name "FPGA_CTL10") (class "Default")
      (node (ref "U7") (pin "K5") (pinfunction "GPIO[27]_K5") (pintype "bidirectional"))
    )
    (net (code "18") (name "FPGA_CTL11") (class "Default")
      (node (ref "U7") (pin "J5") (pinfunction "GPIO[28]_J5") (pintype "bidirectional"))
    )
    (net (code "19") (name "FPGA_CTL12") (class "Default")
      (node (ref "U7") (pin "H5") (pinfunction "GPIO[29]_H5") (pintype "bidirectional"))
    )
    (net (code "20") (name "FPGA_D0") (class "Default")
      (node (ref "J1") (pin "4") (pinfunction "4_4") (pintype "passive"))
      (node (ref "U7") (pin "F10") (pinfunction "GPIO[0]_F10") (pintype "bidirectional"))
    )
    (net (code "21") (name "FPGA_D1") (class "Default")
      (node (ref "J1") (pin "6") (pinfunction "6_6") (pintype "passive"))
      (node (ref "U7") (pin "F9") (pinfunction "GPIO[1]_F9") (pintype "bidirectional"))
    )
    (net (code "22") (name "FPGA_D2") (class "Default")
      (node (ref "J1") (pin "18") (pinfunction "18_18") (pintype "passive"))
      (node (ref "U7") (pin "F7") (pinfunction "GPIO[2]_F7") (pintype "bidirectional"))
    )
    (net (code "23") (name "FPGA_D3") (class "Default")
      (node (ref "J1") (pin "12") (pinfunction "12_12") (pintype "passive"))
      (node (ref "U7") (pin "G10") (pinfunction "GPIO[3]_G10") (pintype "bidirectional"))
    )
    (net (code "24") (name "FPGA_D4") (class "Default")
      (node (ref "J1") (pin "9") (pinfunction "9_9") (pintype "passive"))
      (node (ref "U7") (pin "G9") (pinfunction "GPIO[4]_G9") (pintype "bidirectional"))
    )
    (net (code "25") (name "FPGA_D5") (class "Default")
      (node (ref "J1") (pin "10") (pinfunction "10_10") (pintype "passive"))
      (node (ref "U7") (pin "F8") (pinfunction "GPIO[5]_F8") (pintype "bidirectional"))
    )
    (net (code "26") (name "FPGA_D6") (class "Default")
      (node (ref "J1") (pin "5") (pinfunction "5_5") (pintype "passive"))
      (node (ref "U7") (pin "H10") (pinfunction "GPIO[6]_H10") (pintype "bidirectional"))
    )
    (net (code "27") (name "FPGA_D7") (class "Default")
      (node (ref "J1") (pin "22") (pinfunction "22_22") (pintype "passive"))
      (node (ref "U7") (pin "H9") (pinfunction "GPIO[7]_H9") (pintype "bidirectional"))
    )
    (net (code "28") (name "FPGA_D8") (class "Default")
      (node (ref "J1") (pin "16") (pinfunction "16_16") (pintype "passive"))
      (node (ref "U7") (pin "J10") (pinfunction "GPIO[8]_J10") (pintype "bidirectional"))
    )
    (net (code "29") (name "FPGA_D9") (class "Default")
      (node (ref "J1") (pin "15") (pinfunction "15_15") (pintype "passive"))
      (node (ref "U7") (pin "J9") (pinfunction "GPIO[9]_J9") (pintype "bidirectional"))
    )
    (net (code "30") (name "FPGA_D10") (class "Default")
      (node (ref "J1") (pin "3") (pinfunction "3_3") (pintype "passive"))
      (node (ref "U7") (pin "K11") (pinfunction "GPIO[10]_K11") (pintype "bidirectional"))
    )
    (net (code "31") (name "FPGA_D11") (class "Default")
      (node (ref "J1") (pin "24") (pinfunction "24_24") (pintype "passive"))
      (node (ref "U7") (pin "L10") (pinfunction "GPIO[11]_L10") (pintype "bidirectional"))
    )
    (net (code "32") (name "FPGA_D12") (class "Default")
      (node (ref "J1") (pin "11") (pinfunction "11_11") (pintype "passive"))
      (node (ref "U7") (pin "K10") (pinfunction "GPIO[12]_K10") (pintype "bidirectional"))
    )
    (net (code "33") (name "FPGA_D13") (class "Default")
      (node (ref "J1") (pin "17") (pinfunction "17_17") (pintype "passive"))
      (node (ref "U7") (pin "K9") (pinfunction "GPIO[13]_K9") (pintype "bidirectional"))
    )
    (net (code "34") (name "FPGA_D14") (class "Default")
      (node (ref "J1") (pin "21") (pinfunction "21_21") (pintype "passive"))
      (node (ref "U7") (pin "J8") (pinfunction "GPIO[14]_J8") (pintype "bidirectional"))
    )
    (net (code "35") (name "FPGA_D15") (class "Default")
      (node (ref "J1") (pin "28") (pinfunction "28_28") (pintype "passive"))
      (node (ref "U7") (pin "G8") (pinfunction "GPIO[15]_G8") (pintype "bidirectional"))
    )
    (net (code "36") (name "FPGA_D16") (class "Default")
      (node (ref "J1") (pin "35") (pinfunction "35_35") (pintype "passive"))
      (node (ref "U7") (pin "K2") (pinfunction "GPIO[33]_K2") (pintype "bidirectional"))
    )
    (net (code "37") (name "FPGA_D17") (class "Default")
      (node (ref "J1") (pin "40") (pinfunction "40_40") (pintype "passive"))
      (node (ref "U7") (pin "J4") (pinfunction "GPIO[34]_J4") (pintype "bidirectional"))
    )
    (net (code "38") (name "FPGA_D18") (class "Default")
      (node (ref "J1") (pin "54") (pinfunction "54_54") (pintype "passive"))
      (node (ref "U7") (pin "K1") (pinfunction "GPIO[35]_K1") (pintype "bidirectional"))
    )
    (net (code "39") (name "FPGA_D19") (class "Default")
      (node (ref "J1") (pin "41") (pinfunction "41_41") (pintype "passive"))
      (node (ref "U7") (pin "J2") (pinfunction "GPIO[36]_J2") (pintype "bidirectional"))
    )
    (net (code "40") (name "FPGA_D20") (class "Default")
      (node (ref "J1") (pin "48") (pinfunction "48_48") (pintype "passive"))
      (node (ref "U7") (pin "J3") (pinfunction "GPIO[37]_J3") (pintype "bidirectional"))
    )
    (net (code "41") (name "FPGA_D21") (class "Default")
      (node (ref "J1") (pin "47") (pinfunction "47_47") (pintype "passive"))
      (node (ref "U7") (pin "J1") (pinfunction "GPIO[38]_J1") (pintype "bidirectional"))
    )
    (net (code "42") (name "FPGA_D22") (class "Default")
      (node (ref "J1") (pin "45") (pinfunction "45_45") (pintype "passive"))
      (node (ref "U7") (pin "H2") (pinfunction "GPIO[39]_H2") (pintype "bidirectional"))
    )
    (net (code "43") (name "FPGA_D23") (class "Default")
      (node (ref "J1") (pin "39") (pinfunction "39_39") (pintype "passive"))
      (node (ref "U7") (pin "H3") (pinfunction "GPIO[40]_H3") (pintype "bidirectional"))
    )
    (net (code "44") (name "FPGA_D24") (class "Default")
      (node (ref "J1") (pin "33") (pinfunction "33_33") (pintype "passive"))
      (node (ref "U7") (pin "F4") (pinfunction "GPIO[41]/A0_[5]_F4") (pintype "bidirectional"))
    )
    (net (code "45") (name "FPGA_D25") (class "Default")
      (node (ref "J1") (pin "58") (pinfunction "58_58") (pintype "passive"))
      (node (ref "U7") (pin "G2") (pinfunction "GPIO[42]/A1_[5]_G2") (pintype "bidirectional"))
    )
    (net (code "46") (name "FPGA_D26") (class "Default")
      (node (ref "J1") (pin "52") (pinfunction "52_52") (pintype "passive"))
      (node (ref "U7") (pin "G3") (pinfunction "GPIO[43]_G3") (pintype "bidirectional"))
    )
    (net (code "47") (name "FPGA_D27") (class "Default")
      (node (ref "J1") (pin "51") (pinfunction "51_51") (pintype "passive"))
      (node (ref "U7") (pin "F3") (pinfunction "GPIO[44]_F3") (pintype "bidirectional"))
    )
    (net (code "48") (name "FPGA_D28") (class "Default")
      (node (ref "J1") (pin "53") (pinfunction "53_53") (pintype "passive"))
      (node (ref "U7") (pin "E1") (pinfunction "GPIO[47]_E1") (pintype "bidirectional"))
    )
    (net (code "49") (name "FPGA_D29") (class "Default")
      (node (ref "J1") (pin "27") (pinfunction "27_27") (pintype "passive"))
      (node (ref "U7") (pin "F5") (pinfunction "GPIO[46]_F5") (pintype "bidirectional"))
    )
    (net (code "50") (name "FPGA_D30") (class "Default")
      (node (ref "J1") (pin "42") (pinfunction "42_42") (pintype "passive"))
      (node (ref "U7") (pin "E5") (pinfunction "GPIO[48]_E5") (pintype "bidirectional"))
    )
    (net (code "51") (name "FPGA_D31") (class "Default")
      (node (ref "J1") (pin "46") (pinfunction "46_46") (pintype "passive"))
      (node (ref "U7") (pin "E4") (pinfunction "GPIO[49]_E4") (pintype "bidirectional"))
    )
    (net (code "52") (name "FPGA_PCLK") (class "Default")
      (node (ref "J1") (pin "29") (pinfunction "29_29") (pintype "passive"))
      (node (ref "U7") (pin "J6") (pinfunction "GPIO[16]_J6") (pintype "bidirectional"))
    )
    (net (code "53") (name "FX3_RXN") (class "Default")
      (node (ref "U6") (pin "1") (pinfunction "A0N_1") (pintype "bidirectional"))
      (node (ref "U7") (pin "A3") (pinfunction "SSRXM_A3") (pintype "input"))
    )
    (net (code "54") (name "FX3_RXP") (class "Default")
      (node (ref "U6") (pin "16") (pinfunction "A0P_16") (pintype "bidirectional"))
      (node (ref "U7") (pin "A4") (pinfunction "SSRXP_A4") (pintype "input"))
    )
    (net (code "55") (name "FX3_TX_N") (class "Default")
      (node (ref "U6") (pin "5") (pinfunction "A1N_5") (pintype "bidirectional"))
      (node (ref "U7") (pin "A6") (pinfunction "SSTXM_A6") (pintype "output"))
    )
    (net (code "56") (name "FX3_TX_P") (class "Default")
      (node (ref "U6") (pin "4") (pinfunction "A1P_4") (pintype "bidirectional"))
      (node (ref "U7") (pin "A5") (pinfunction "SSTXP_A5") (pintype "output"))
    )
    (net (code "57") (name "GND") (class "Default")
      (node (ref "C1") (pin "2") (pinfunction "2_2") (pintype "passive"))
      (node (ref "C10") (pin "2") (pinfunction "2_2") (pintype "passive"))
      (node (ref "C11") (pin "2") (pinfunction "2_2") (pintype "passive"))
      (node (ref "C12") (pin "2") (pinfunction "2_2") (pintype "passive"))
      (node (ref "C13") (pin "2") (pinfunction "2_2") (pintype "passive"))
      (node (ref "C14") (pin "2") (pinfunction "2_2") (pintype "passive"))
      (node (ref "C15") (pin "2") (pinfunction "2_2") (pintype "passive"))
      (node (ref "C16") (pin "2") (pinfunction "2_2") (pintype "passive"))
      (node (ref "C17") (pin "2") (pinfunction "2_2") (pintype "passive"))
      (node (ref "C18") (pin "2") (pinfunction "2_2") (pintype "passive"))
      (node (ref "C19") (pin "2") (pinfunction "2_2") (pintype "passive"))
      (node (ref "C2") (pin "2") (pinfunction "2_2") (pintype "passive"))
      (node (ref "C20") (pin "2") (pinfunction "2_2") (pintype "passive"))
      (node (ref "C21") (pin "2") (pinfunction "2_2") (pintype "passive"))
      (node (ref "C22") (pin "2") (pinfunction "2_2") (pintype "passive"))
      (node (ref "C23") (pin "2") (pinfunction "2_2") (pintype "passive"))
      (node (ref "C24") (pin "2") (pinfunction "2_2") (pintype "passive"))
      (node (ref "C25") (pin "2") (pinfunction "2_2") (pintype "passive"))
      (node (ref "C26") (pin "2") (pinfunction "2_2") (pintype "passive"))
      (node (ref "C27") (pin "2") (pinfunction "2_2") (pintype "passive"))
      (node (ref "C28") (pin "2") (pinfunction "2_2") (pintype "passive"))
      (node (ref "C29") (pin "2") (pinfunction "2_2") (pintype "passive"))
      (node (ref "C3") (pin "2") (pinfunction "2_2") (pintype "passive"))
      (node (ref "C30") (pin "2") (pinfunction "2_2") (pintype "passive"))
      (node (ref "C31") (pin "2") (pinfunction "2_2") (pintype "passive"))
      (node (ref "C32") (pin "2") (pinfunction "2_2") (pintype "passive"))
      (node (ref "C33") (pin "2") (pinfunction "2_2") (pintype "passive"))
      (node (ref "C34") (pin "2") (pinfunction "2_2") (pintype "passive"))
      (node (ref "C35") (pin "2") (pinfunction "2_2") (pintype "passive"))
      (node (ref "C36") (pin "2") (pinfunction "2_2") (pintype "passive"))
      (node (ref "C37") (pin "2") (pinfunction "2_2") (pintype "passive"))
      (node (ref "C38") (pin "2") (pinfunction "2_2") (pintype "passive"))
      (node (ref "C39") (pin "1") (pinfunction "1_1") (pintype "passive"))
      (node (ref "C4") (pin "2") (pinfunction "2_2") (pintype "passive"))
      (node (ref "C5") (pin "2") (pinfunction "2_2") (pintype "passive"))
      (node (ref "C6") (pin "2") (pinfunction "2_2") (pintype "passive"))
      (node (ref "C7") (pin "2") (pinfunction "2_2") (pintype "passive"))
      (node (ref "C8") (pin "2") (pinfunction "2_2") (pintype "passive"))
      (node (ref "C9") (pin "2") (pinfunction "2_2") (pintype "passive"))
      (node (ref "D1") (pin "3") (pinfunction "3_3") (pintype "passive"))
      (node (ref "D1") (pin "8") (pinfunction "8_8") (pintype "passive"))
      (node (ref "D2") (pin "3") (pinfunction "3_3") (pintype "passive"))
      (node (ref "D2") (pin "8") (pinfunction "8_8") (pintype "passive"))
      (node (ref "D3") (pin "3") (pinfunction "3_3") (pintype "passive"))
      (node (ref "D3") (pin "8") (pinfunction "8_8") (pintype "passive"))
      (node (ref "J1") (pin "1") (pinfunction "1_1") (pintype "passive"))
      (node (ref "J1") (pin "13") (pinfunction "13_13") (pintype "passive"))
      (node (ref "J1") (pin "14") (pinfunction "14_14") (pintype "passive"))
      (node (ref "J1") (pin "19") (pinfunction "19_19") (pintype "passive"))
      (node (ref "J1") (pin "2") (pinfunction "2_2") (pintype "passive"))
      (node (ref "J1") (pin "20") (pinfunction "20_20") (pintype "passive"))
      (node (ref "J1") (pin "25") (pinfunction "25_25") (pintype "passive"))
      (node (ref "J1") (pin "26") (pinfunction "26_26") (pintype "passive"))
      (node (ref "J1") (pin "31") (pinfunction "31_31") (pintype "passive"))
      (node (ref "J1") (pin "32") (pinfunction "32_32") (pintype "passive"))
      (node (ref "J1") (pin "37") (pinfunction "37_37") (pintype "passive"))
      (node (ref "J1") (pin "38") (pinfunction "38_38") (pintype "passive"))
      (node (ref "J1") (pin "43") (pinfunction "43_43") (pintype "passive"))
      (node (ref "J1") (pin "44") (pinfunction "44_44") (pintype "passive"))
      (node (ref "J1") (pin "49") (pinfunction "49_49") (pintype "passive"))
      (node (ref "J1") (pin "50") (pinfunction "50_50") (pintype "passive"))
      (node (ref "J1") (pin "55") (pinfunction "55_55") (pintype "passive"))
      (node (ref "J1") (pin "56") (pinfunction "56_56") (pintype "passive"))
      (node (ref "J1") (pin "59") (pinfunction "59_59") (pintype "passive"))
      (node (ref "J1") (pin "60") (pinfunction "60_60") (pintype "passive"))
      (node (ref "J1") (pin "7") (pinfunction "7_7") (pintype "passive"))
      (node (ref "J1") (pin "8") (pinfunction "8_8") (pintype "passive"))
      (node (ref "J1") (pin "S1") (pinfunction "SHIELD_S1") (pintype "passive"))
      (node (ref "J1") (pin "S2") (pinfunction "SHIELD_S2") (pintype "passive"))
      (node (ref "J2") (pin "A1") (pinfunction "GND_A1") (pintype "power_in"))
      (node (ref "J2") (pin "A12") (pinfunction "GND_A12") (pintype "power_in"))
      (node (ref "J2") (pin "B1") (pinfunction "GND_B1") (pintype "power_in"))
      (node (ref "J2") (pin "B12") (pinfunction "GND_B12") (pintype "power_in"))
      (node (ref "JTAG") (pin "2") (pinfunction "2_2") (pintype "passive"))
      (node (ref "R13") (pin "1") (pinfunction "1_1") (pintype "passive"))
      (node (ref "R15") (pin "2") (pinfunction "2_2") (pintype "passive"))
      (node (ref "R16") (pin "2") (pinfunction "2_2") (pintype "passive"))
      (node (ref "R17") (pin "2") (pinfunction "2_2") (pintype "passive"))
      (node (ref "R18") (pin "2") (pinfunction "2_2") (pintype "passive"))
      (node (ref "R19") (pin "2") (pinfunction "2_2") (pintype "passive"))
      (node (ref "R21") (pin "2") (pinfunction "2_2") (pintype "passive"))
      (node (ref "R22") (pin "1") (pinfunction "1_1") (pintype "passive"))
      (node (ref "R23") (pin "2") (pinfunction "2_2") (pintype "passive"))
      (node (ref "R3") (pin "1") (pinfunction "1_1") (pintype "passive"))
      (node (ref "R6") (pin "1") (pinfunction "1_1") (pintype "passive"))
      (node (ref "R8") (pin "1") (pinfunction "1_1") (pintype "passive"))
      (node (ref "R9") (pin "1") (pinfunction "1_1") (pintype "passive"))
      (node (ref "T2") (pin "P$1") (pinfunction "P$1_P$1") (pintype "bidirectional"))
      (node (ref "U1") (pin "1") (pinfunction "GND_1") (pintype "bidirectional"))
      (node (ref "U2") (pin "1") (pinfunction "GND_1") (pintype "bidirectional"))
      (node (ref "U3") (pin "1") (pinfunction "GND_1") (pintype "bidirectional"))
      (node (ref "U4") (pin "3") (pinfunction "A2_3") (pintype "input"))
      (node (ref "U4") (pin "4") (pinfunction "GND_4") (pintype "power_in"))
      (node (ref "U4") (pin "7") (pinfunction "WP_7") (pintype "input"))
      (node (ref "U5") (pin "2") (pinfunction "GND_2") (pintype "power_in"))
      (node (ref "U5") (pin "3") (pinfunction "~{EN}_3") (pintype "input"))
      (node (ref "U6") (pin "2") (pinfunction "GND_2") (pintype "power_in"))
      (node (ref "U7") (pin "A1") (pinfunction "U3VSSQ_A1") (pintype "passive"))
      (node (ref "U7") (pin "A8") (pinfunction "VSS_2_A8") (pintype "passive"))
      (node (ref "U7") (pin "B2") (pinfunction "FSLC[0]_B2") (pintype "bidirectional"))
      (node (ref "U7") (pin "B4") (pinfunction "FSLC[1]_B4") (pintype "bidirectional"))
      (node (ref "U7") (pin "B7") (pinfunction "AVSS_B7") (pintype "passive"))
      (node (ref "U7") (pin "B8") (pinfunction "VSS_3_B8") (pintype "passive"))
      (node (ref "U7") (pin "B9") (pinfunction "VSS_4_B9") (pintype "passive"))
      (node (ref "U7") (pin "D8") (pinfunction "VSS_5_D8") (pintype "passive"))
      (node (ref "U7") (pin "E2") (pinfunction "VSS_E2") (pintype "passive"))
      (node (ref "U7") (pin "E6") (pinfunction "FSLC[2]_E6") (pintype "input"))
      (node (ref "U7") (pin "G1") (pinfunction "VSS_2_G1") (pintype "passive"))
      (node (ref "U7") (pin "G11") (pinfunction "VSS_3_G11") (pintype "passive"))
      (node (ref "U7") (pin "K3") (pinfunction "VSS_4_K3") (pintype "passive"))
      (node (ref "U7") (pin "K4") (pinfunction "VSS_5_K4") (pintype "passive"))
      (node (ref "U7") (pin "L1") (pinfunction "VSS_6_L1") (pintype "passive"))
      (node (ref "U7") (pin "L11") (pinfunction "VSS_L11") (pintype "passive"))
      (node (ref "U7") (pin "L2") (pinfunction "VSS_7_L2") (pintype "passive"))
      (node (ref "U7") (pin "L3") (pinfunction "VSS_8_L3") (pintype "passive"))
      (node (ref "U7") (pin "L6") (pinfunction "VSS_9_L6") (pintype "passive"))
    )
    (net (code "58") (name "LED") (class "Default")
      (node (ref "LED2") (pin "A") (pinfunction "A_A") (pintype "passive"))
      (node (ref "U7") (pin "D11") (pinfunction "O[60]_D11") (pintype "output"))
    )
    (net (code "59") (name "Net-(C39-Pad2)") (class "Default")
      (node (ref "C39") (pin "2") (pinfunction "2_2") (pintype "passive"))
      (node (ref "J2") (pin "S_1_H1") (pinfunction "SHIELD_S_1_H1") (pintype "bidirectional"))
      (node (ref "J2") (pin "S_1_H2") (pinfunction "SHIELD_S_1_H2") (pintype "bidirectional"))
      (node (ref "J2") (pin "S_2_H1") (pinfunction "SHIELD_S_2_H1") (pintype "bidirectional"))
      (node (ref "J2") (pin "S_2_H2") (pinfunction "SHIELD_S_2_H2") (pintype "bidirectional"))
      (node (ref "J2") (pin "S_3_H1") (pinfunction "SHIELD_S_3_H1") (pintype "bidirectional"))
      (node (ref "J2") (pin "S_3_H2") (pinfunction "SHIELD_S_3_H2") (pintype "bidirectional"))
      (node (ref "J2") (pin "S_4_H1") (pinfunction "SHIELD_S_4_H1") (pintype "bidirectional"))
      (node (ref "J2") (pin "S_4_H2") (pinfunction "SHIELD_S_4_H2") (pintype "bidirectional"))
      (node (ref "R15") (pin "1") (pinfunction "1_1") (pintype "passive"))
    )
    (net (code "60") (name "Net-(J2-CC1)") (class "Default")
      (node (ref "J2") (pin "A5") (pinfunction "CC1_A5") (pintype "bidirectional"))
      (node (ref "R16") (pin "1") (pinfunction "1_1") (pintype "passive"))
    )
    (net (code "61") (name "Net-(J2-CC2)") (class "Default")
      (node (ref "J2") (pin "B5") (pinfunction "CC2_B5") (pintype "bidirectional"))
      (node (ref "R21") (pin "1") (pinfunction "1_1") (pintype "passive"))
    )
    (net (code "62") (name "Net-(LED1-PadC)") (class "Default")
      (node (ref "LED1") (pin "C") (pinfunction "C_C") (pintype "passive"))
      (node (ref "R17") (pin "1") (pinfunction "1_1") (pintype "passive"))
    )
    (net (code "63") (name "Net-(LED2-PadC)") (class "Default")
      (node (ref "LED2") (pin "C") (pinfunction "C_C") (pintype "passive"))
      (node (ref "R18") (pin "1") (pinfunction "1_1") (pintype "passive"))
    )
    (net (code "64") (name "Net-(LED3-PadC)") (class "Default")
      (node (ref "LED3") (pin "C") (pinfunction "C_C") (pintype "passive"))
      (node (ref "R19") (pin "1") (pinfunction "1_1") (pintype "passive"))
    )
    (net (code "65") (name "Net-(R20-Pad1)") (class "Default")
      (node (ref "R20") (pin "1") (pinfunction "1_1") (pintype "passive"))
      (node (ref "T1") (pin "P$2") (pinfunction "P$2_P$2") (pintype "bidirectional"))
    )
    (net (code "66") (name "Net-(U1-FB)") (class "Default")
      (node (ref "R3") (pin "2") (pinfunction "2_2") (pintype "passive"))
      (node (ref "R4") (pin "2") (pinfunction "2_2") (pintype "passive"))
      (node (ref "U1") (pin "5") (pinfunction "FB_5") (pintype "bidirectional"))
    )
    (net (code "67") (name "Net-(U1-SW)") (class "Default")
      (node (ref "L1") (pin "2") (pinfunction "2_2") (pintype "passive"))
      (node (ref "U1") (pin "2") (pinfunction "SW_2") (pintype "bidirectional"))
    )
    (net (code "68") (name "Net-(U2-FB)") (class "Default")
      (node (ref "R12") (pin "2") (pinfunction "2_2") (pintype "passive"))
      (node (ref "R9") (pin "2") (pinfunction "2_2") (pintype "passive"))
      (node (ref "U2") (pin "5") (pinfunction "FB_5") (pintype "bidirectional"))
    )
    (net (code "69") (name "Net-(U2-SW)") (class "Default")
      (node (ref "L5") (pin "2") (pinfunction "2_2") (pintype "passive"))
      (node (ref "U2") (pin "2") (pinfunction "SW_2") (pintype "bidirectional"))
    )
    (net (code "70") (name "Net-(U3-FB)") (class "Default")
      (node (ref "R13") (pin "2") (pinfunction "2_2") (pintype "passive"))
      (node (ref "R14") (pin "2") (pinfunction "2_2") (pintype "passive"))
      (node (ref "U3") (pin "5") (pinfunction "FB_5") (pintype "bidirectional"))
    )
    (net (code "71") (name "Net-(U3-SW)") (class "Default")
      (node (ref "L7") (pin "2") (pinfunction "2_2") (pintype "passive"))
      (node (ref "U3") (pin "2") (pinfunction "SW_2") (pintype "bidirectional"))
    )
    (net (code "72") (name "Net-(U6-B1N)") (class "Default")
      (node (ref "C41") (pin "2") (pinfunction "2_2") (pintype "passive"))
      (node (ref "U6") (pin "11") (pinfunction "B1N_11") (pintype "bidirectional"))
    )
    (net (code "73") (name "Net-(U6-B1P)") (class "Default")
      (node (ref "C43") (pin "2") (pinfunction "2_2") (pintype "passive"))
      (node (ref "U6") (pin "12") (pinfunction "B1P_12") (pintype "bidirectional"))
    )
    (net (code "74") (name "Net-(U6-C1N)") (class "Default")
      (node (ref "C42") (pin "2") (pinfunction "2_2") (pintype "passive"))
      (node (ref "U6") (pin "7") (pinfunction "C1N_7") (pintype "bidirectional"))
    )
    (net (code "75") (name "Net-(U6-C1P)") (class "Default")
      (node (ref "C40") (pin "2") (pinfunction "2_2") (pintype "passive"))
      (node (ref "U6") (pin "8") (pinfunction "C1P_8") (pintype "bidirectional"))
    )
    (net (code "76") (name "Net-(U7A-R_USB2)") (class "Default")
      (node (ref "R6") (pin "2") (pinfunction "2_2") (pintype "passive"))
      (node (ref "U7") (pin "C8") (pinfunction "R_USB2_C8") (pintype "bidirectional"))
    )
    (net (code "77") (name "Net-(U7A-R_USB3)") (class "Default")
      (node (ref "R8") (pin "2") (pinfunction "2_2") (pintype "passive"))
      (node (ref "U7") (pin "B3") (pinfunction "R_USB3_B3") (pintype "bidirectional"))
    )
    (net (code "78") (name "PMODE0") (class "Default")
      (node (ref "R20") (pin "2") (pinfunction "2_2") (pintype "passive"))
      (node (ref "R5") (pin "2") (pinfunction "2_2") (pintype "passive"))
      (node (ref "U7") (pin "G4") (pinfunction "GPIO[30]_G4") (pintype "bidirectional"))
    )
    (net (code "79") (name "PMODE1") (class "Default")
      (node (ref "R2") (pin "2") (pinfunction "2_2") (pintype "passive"))
      (node (ref "U7") (pin "H4") (pinfunction "GPIO[31]_H4") (pintype "bidirectional"))
    )
    (net (code "80") (name "PMODE2") (class "Default")
      (node (ref "R1") (pin "2") (pinfunction "2_2") (pintype "passive"))
      (node (ref "U7") (pin "L4") (pinfunction "GPIO[32]_L4") (pintype "bidirectional"))
    )
    (net (code "81") (name "RESET") (class "Default")
      (node (ref "C19") (pin "1") (pinfunction "1_1") (pintype "passive"))
      (node (ref "R7") (pin "2") (pinfunction "2_2") (pintype "passive"))
      (node (ref "T2") (pin "P$2") (pinfunction "P$2_P$2") (pintype "bidirectional"))
      (node (ref "U7") (pin "C5") (pinfunction "RESET_C5") (pintype "input"))
    )
    (net (code "82") (name "RXVDDQ") (class "Default")
      (node (ref "C25") (pin "1") (pinfunction "1_1") (pintype "passive"))
      (node (ref "C26") (pin "1") (pinfunction "1_1") (pintype "passive"))
      (node (ref "L2") (pin "2") (pinfunction "2_2") (pintype "passive"))
      (node (ref "U7") (pin "A2") (pinfunction "U3RXVDDQ_A2") (pintype "power_in"))
    )
    (net (code "83") (name "SCL_1V8") (class "Default")
      (node (ref "R10") (pin "2") (pinfunction "2_2") (pintype "passive"))
      (node (ref "U4") (pin "6") (pinfunction "SCL_6") (pintype "bidirectional"))
      (node (ref "U7") (pin "D9") (pinfunction "I2C_GPIO[58]_D9") (pintype "bidirectional"))
    )
    (net (code "84") (name "SDA_1V8") (class "Default")
      (node (ref "R11") (pin "2") (pinfunction "2_2") (pintype "passive"))
      (node (ref "U4") (pin "5") (pinfunction "SDA_5") (pintype "bidirectional"))
      (node (ref "U7") (pin "D10") (pinfunction "I2C_GPIO[59]_D10") (pintype "bidirectional"))
    )
    (net (code "85") (name "TCK") (class "Default")
      (node (ref "JTAG") (pin "3") (pinfunction "3_3") (pintype "passive"))
      (node (ref "U7") (pin "F6") (pinfunction "TCK_F6") (pintype "input"))
    )
    (net (code "86") (name "TDI") (class "Default")
      (node (ref "JTAG") (pin "5") (pinfunction "5_5") (pintype "passive"))
      (node (ref "U7") (pin "E7") (pinfunction "TDI_E7") (pintype "input"))
    )
    (net (code "87") (name "TDO") (class "Default")
      (node (ref "JTAG") (pin "4") (pinfunction "4_4") (pintype "passive"))
      (node (ref "U7") (pin "C10") (pinfunction "TDO_C10") (pintype "output"))
    )
    (net (code "88") (name "TMS") (class "Default")
      (node (ref "JTAG") (pin "6") (pinfunction "6_6") (pintype "passive"))
      (node (ref "U7") (pin "E8") (pinfunction "TMS_E8") (pintype "input"))
    )
    (net (code "89") (name "TRST") (class "Default")
      (node (ref "JTAG") (pin "7") (pinfunction "7_7") (pintype "passive"))
      (node (ref "U7") (pin "B11") (pinfunction "TRST_B11") (pintype "input"))
    )
    (net (code "90") (name "TXVDDQ") (class "Default")
      (node (ref "C27") (pin "1") (pinfunction "1_1") (pintype "passive"))
      (node (ref "C28") (pin "1") (pinfunction "1_1") (pintype "passive"))
      (node (ref "L3") (pin "2") (pinfunction "2_2") (pintype "passive"))
      (node (ref "U7") (pin "B5") (pinfunction "U3TXVDDQ_B5") (pintype "power_in"))
    )
    (net (code "91") (name "UART_CTS") (class "Default")
      (node (ref "J1") (pin "63") (pinfunction "63_63") (pintype "passive"))
      (node (ref "U7") (pin "C1") (pinfunction "GPIO[54]_C1") (pintype "bidirectional"))
    )
    (net (code "92") (name "UART_RTS") (class "Default")
      (node (ref "J1") (pin "61") (pinfunction "61_61") (pintype "passive"))
      (node (ref "U7") (pin "D4") (pinfunction "GPIO[53]_D4") (pintype "bidirectional"))
    )
    (net (code "93") (name "UART_RX") (class "Default")
      (node (ref "J1") (pin "62") (pinfunction "62_62") (pintype "passive"))
      (node (ref "U7") (pin "D5") (pinfunction "GPIO[56]_D5") (pintype "bidirectional"))
    )
    (net (code "94") (name "UART_TX") (class "Default")
      (node (ref "J1") (pin "64") (pinfunction "64_64") (pintype "passive"))
      (node (ref "U7") (pin "C2") (pinfunction "GPIO[55]_C2") (pintype "bidirectional"))
    )
    (net (code "95") (name "USB3_MUX_SEL") (class "Default")
      (node (ref "U6") (pin "6") (pinfunction "SEL_6") (pintype "input"))
      (node (ref "U7") (pin "D3") (pinfunction "GPIO[52]_D3") (pintype "bidirectional"))
    )
    (net (code "96") (name "USB3_MUX_~{OE}") (class "Default")
      (node (ref "R22") (pin "2") (pinfunction "2_2") (pintype "passive"))
      (node (ref "U6") (pin "15") (pinfunction "~{OE}_15") (pintype "input"))
      (node (ref "U7") (pin "D1") (pinfunction "GPIO[50]_D1") (pintype "bidirectional"))
    )
    (net (code "97") (name "USB_D_N") (class "Default")
      (node (ref "D3") (pin "5") (pinfunction "5_5") (pintype "passive"))
      (node (ref "D3") (pin "6") (pinfunction "6_6") (pintype "passive"))
      (node (ref "J2") (pin "A7") (pinfunction "DN1_A7") (pintype "bidirectional"))
      (node (ref "J2") (pin "B7") (pinfunction "DN2_B7") (pintype "bidirectional"))
      (node (ref "U7") (pin "A10") (pinfunction "DM_A10") (pintype "bidirectional"))
    )
    (net (code "98") (name "USB_D_P") (class "Default")
      (node (ref "D3") (pin "4") (pinfunction "4_4") (pintype "passive"))
      (node (ref "D3") (pin "7") (pinfunction "7_7") (pintype "passive"))
      (node (ref "J2") (pin "A6") (pinfunction "DP1_A6") (pintype "bidirectional"))
      (node (ref "J2") (pin "B6") (pinfunction "DP2_B6") (pintype "bidirectional"))
      (node (ref "U7") (pin "A9") (pinfunction "DP_A9") (pintype "bidirectional"))
    )
    (net (code "99") (name "USB_RX1_N") (class "Default")
      (node (ref "D1") (pin "5") (pinfunction "5_5") (pintype "passive"))
      (node (ref "D1") (pin "6") (pinfunction "6_6") (pintype "passive"))
      (node (ref "J2") (pin "B10") (pinfunction "RXN1_B10") (pintype "bidirectional"))
      (node (ref "U6") (pin "13") (pinfunction "B0N_13") (pintype "bidirectional"))
    )
    (net (code "100") (name "USB_RX1_P") (class "Default")
      (node (ref "D1") (pin "4") (pinfunction "4_4") (pintype "passive"))
      (node (ref "D1") (pin "7") (pinfunction "7_7") (pintype "passive"))
      (node (ref "J2") (pin "B11") (pinfunction "RXP1_B11") (pintype "bidirectional"))
      (node (ref "U6") (pin "14") (pinfunction "B0P_14") (pintype "bidirectional"))
    )
    (net (code "101") (name "USB_RX2_N") (class "Default")
      (node (ref "D2") (pin "1") (pinfunction "1_1") (pintype "passive"))
      (node (ref "D2") (pin "10") (pinfunction "10_10") (pintype "passive"))
      (node (ref "J2") (pin "A10") (pinfunction "RXN2_A10") (pintype "bidirectional"))
      (node (ref "U6") (pin "9") (pinfunction "C0N_9") (pintype "bidirectional"))
    )
    (net (code "102") (name "USB_RX2_P") (class "Default")
      (node (ref "D2") (pin "2") (pinfunction "2_2") (pintype "passive"))
      (node (ref "D2") (pin "9") (pinfunction "9_9") (pintype "passive"))
      (node (ref "J2") (pin "A11") (pinfunction "RXP2_A11") (pintype "bidirectional"))
      (node (ref "U6") (pin "10") (pinfunction "C0P_10") (pintype "bidirectional"))
    )
    (net (code "103") (name "USB_TX1_N") (class "Default")
      (node (ref "C41") (pin "1") (pinfunction "1_1") (pintype "passive"))
      (node (ref "D1") (pin "2") (pinfunction "2_2") (pintype "passive"))
      (node (ref "D1") (pin "9") (pinfunction "9_9") (pintype "passive"))
      (node (ref "J2") (pin "A3") (pinfunction "TXN1_A3") (pintype "bidirectional"))
    )
    (net (code "104") (name "USB_TX1_P") (class "Default")
      (node (ref "C43") (pin "1") (pinfunction "1_1") (pintype "passive"))
      (node (ref "D1") (pin "1") (pinfunction "1_1") (pintype "passive"))
      (node (ref "D1") (pin "10") (pinfunction "10_10") (pintype "passive"))
      (node (ref "J2") (pin "A2") (pinfunction "TXP1_A2") (pintype "bidirectional"))
    )
    (net (code "105") (name "USB_TX2_N") (class "Default")
      (node (ref "C42") (pin "1") (pinfunction "1_1") (pintype "passive"))
      (node (ref "D2") (pin "4") (pinfunction "4_4") (pintype "passive"))
      (node (ref "D2") (pin "7") (pinfunction "7_7") (pintype "passive"))
      (node (ref "J2") (pin "B3") (pinfunction "TXN2_B3") (pintype "bidirectional"))
    )
    (net (code "106") (name "USB_TX2_P") (class "Default")
      (node (ref "C40") (pin "1") (pinfunction "1_1") (pintype "passive"))
      (node (ref "D2") (pin "5") (pinfunction "5_5") (pintype "passive"))
      (node (ref "D2") (pin "6") (pinfunction "6_6") (pintype "passive"))
      (node (ref "J2") (pin "B2") (pinfunction "TXP2_B2") (pintype "bidirectional"))
    )
    (net (code "107") (name "VBATT") (class "Default")
      (node (ref "U7") (pin "E10") (pinfunction "VBATT_E10") (pintype "power_in"))
    )
    (net (code "108") (name "VBUS") (class "Default")
      (node (ref "J2") (pin "A4") (pinfunction "VBUS_A4") (pintype "power_in"))
      (node (ref "J2") (pin "A9") (pinfunction "VBUS_A9") (pintype "power_in"))
      (node (ref "J2") (pin "B4") (pinfunction "VBUS_B4") (pintype "power_in"))
      (node (ref "J2") (pin "B9") (pinfunction "VBUS_B9") (pintype "power_in"))
      (node (ref "U5") (pin "1") (pinfunction "IN_1") (pintype "input"))
    )
    (net (code "109") (name "VIO") (class "Default")
      (node (ref "C14") (pin "1") (pinfunction "1_1") (pintype "passive"))
      (node (ref "C16") (pin "1") (pinfunction "1_1") (pintype "passive"))
      (node (ref "C3") (pin "1") (pinfunction "1_1") (pintype "passive"))
      (node (ref "C8") (pin "1") (pinfunction "1_1") (pintype "passive"))
      (node (ref "R1") (pin "1") (pinfunction "1_1") (pintype "passive"))
      (node (ref "R2") (pin "1") (pinfunction "1_1") (pintype "passive"))
      (node (ref "R5") (pin "1") (pinfunction "1_1") (pintype "passive"))
      (node (ref "T1") (pin "P$1") (pinfunction "P$1_P$1") (pintype "bidirectional"))
      (node (ref "T3") (pin "P$1") (pinfunction "P$1_P$1") (pintype "bidirectional"))
      (node (ref "U7") (pin "B1") (pinfunction "VIO4_B1") (pintype "bidirectional"))
      (node (ref "U7") (pin "E3") (pinfunction "VIO3_E3") (pintype "bidirectional"))
      (node (ref "U7") (pin "F1") (pinfunction "VIO2_F1") (pintype "bidirectional"))
      (node (ref "U7") (pin "H11") (pinfunction "VIO1_2_H11") (pintype "bidirectional"))
      (node (ref "U7") (pin "L9") (pinfunction "VIO1_L9") (pintype "bidirectional"))
      (node (ref "VIO") (pin "2") (pinfunction "2_2") (pintype "passive"))
    )
    (net (code "110") (name "XTAL_IN") (class "Default")
      (node (ref "C20") (pin "1") (pinfunction "1_1") (pintype "passive"))
      (node (ref "U7") (pin "C6") (pinfunction "XTALIN_C6") (pintype "bidirectional"))
      (node (ref "X1") (pin "1") (pinfunction "1_1") (pintype "passive"))
    )
    (net (code "111") (name "XTAL_OUT") (class "Default")
      (node (ref "C10") (pin "1") (pinfunction "1_1") (pintype "passive"))
      (node (ref "U7") (pin "C7") (pinfunction "XTALOUT_C7") (pintype "bidirectional"))
      (node (ref "X1") (pin "3") (pinfunction "2_3") (pintype "passive"))
    )
    (net (code "112") (name "unconnected-(D3-Pad1)") (class "Default")
      (node (ref "D3") (pin "1") (pinfunction "1_1") (pintype "passive"))
    )
    (net (code "113") (name "unconnected-(D3-Pad2)") (class "Default")
      (node (ref "D3") (pin "2") (pinfunction "2_2") (pintype "passive"))
    )
    (net (code "114") (name "unconnected-(D3-Pad9)") (class "Default")
      (node (ref "D3") (pin "9") (pinfunction "9_9") (pintype "passive"))
    )
    (net (code "115") (name "unconnected-(D3-Pad10)") (class "Default")
      (node (ref "D3") (pin "10") (pinfunction "10_10") (pintype "passive"))
    )
    (net (code "116") (name "unconnected-(J1-Pad57)") (class "Default")
      (node (ref "J1") (pin "57") (pinfunction "57_57") (pintype "passive"))
    )
    (net (code "117") (name "unconnected-(J2-SBU1-PadA8)") (class "Default")
      (node (ref "J2") (pin "A8") (pinfunction "SBU1_A8") (pintype "bidirectional"))
    )
    (net (code "118") (name "unconnected-(J2-SBU2-PadB8)") (class "Default")
      (node (ref "J2") (pin "B8") (pinfunction "SBU2_B8") (pintype "bidirectional"))
    )
    (net (code "119") (name "unconnected-(U1-PG-Pad6)") (class "Default")
      (node (ref "U1") (pin "6") (pinfunction "PG_6") (pintype "bidirectional"))
    )
    (net (code "120") (name "unconnected-(U2-PG-Pad6)") (class "Default")
      (node (ref "U2") (pin "6") (pinfunction "PG_6") (pintype "bidirectional"))
    )
    (net (code "121") (name "unconnected-(U3-PG-Pad6)") (class "Default")
      (node (ref "U3") (pin "6") (pinfunction "PG_6") (pintype "bidirectional"))
    )
    (net (code "122") (name "unconnected-(U5-~{FLAG}-Pad4)") (class "Default")
      (node (ref "U5") (pin "4") (pinfunction "~{FLAG}_4") (pintype "passive"))
    )
    (net (code "123") (name "unconnected-(U7A-CLKIN-PadD7)") (class "Default")
      (node (ref "U7") (pin "D7") (pinfunction "CLKIN_D7") (pintype "input"))
    )
    (net (code "124") (name "unconnected-(U7A-CLKIN_32-PadD6)") (class "Default")
      (node (ref "U7") (pin "D6") (pinfunction "CLKIN_32_D6") (pintype "input"))
    )
    (net (code "125") (name "unconnected-(U7A-GPIO[45]-PadF2)") (class "Default")
      (node (ref "U7") (pin "F2") (pinfunction "GPIO[45]_F2") (pintype "bidirectional"))
    )
    (net (code "126") (name "unconnected-(U7A-GPIO[51]-PadD2)") (class "Default")
      (node (ref "U7") (pin "D2") (pinfunction "GPIO[51]_D2") (pintype "bidirectional"))
    )
    (net (code "127") (name "unconnected-(U7A-GPIO[57]-PadC4)") (class "Default")
      (node (ref "U7") (pin "C4") (pinfunction "GPIO[57]_C4") (pintype "bidirectional"))
    )
    (net (code "128") (name "unconnected-(U7A-NC-PadA11)") (class "Default")
      (node (ref "U7") (pin "A11") (pinfunction "NC_A11") (pintype "no_connect"))
    )
    (net (code "129") (name "unconnected-(U7A-OTG_ID-PadC9)") (class "Default")
      (node (ref "U7") (pin "C9") (pinfunction "OTG_ID_C9") (pintype "input"))
    )
    (net (code "130") (name "unconnected-(U7B-INT-PadL8)") (class "Default")
      (node (ref "U7") (pin "L8") (pinfunction "INT_L8") (pintype "input"))
    )
  )
)
